# Steuerung.net
KiCad netlist of a schematic drawn in EAGLE
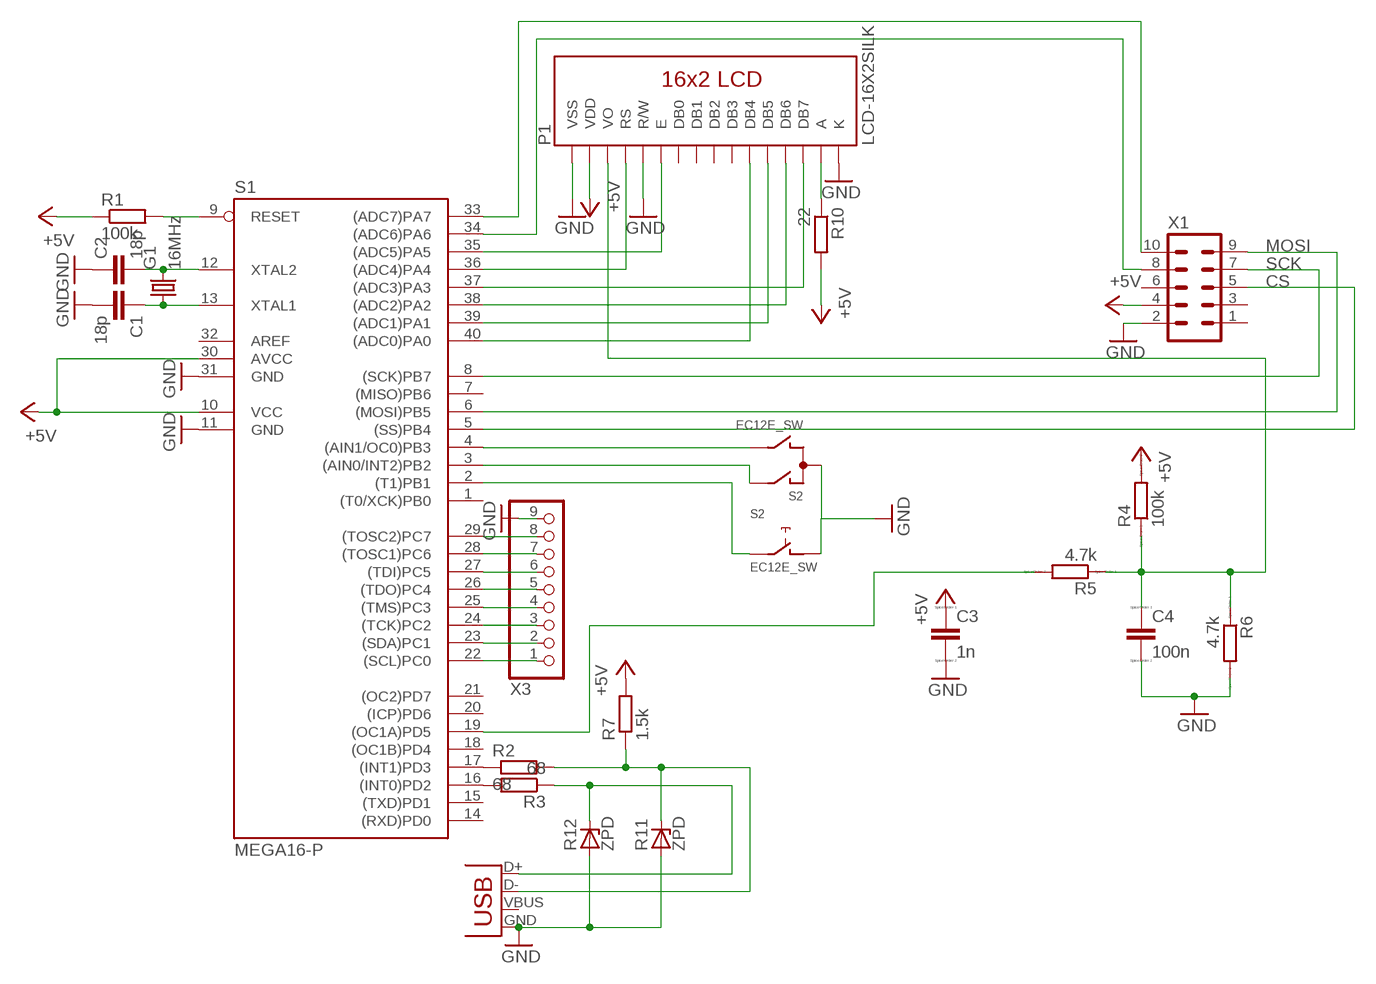
[diagram p0: schematic, sheet 1]

(export (version "E")
  (design (tool "Eeschema 10.0.6"))
  (components
    (comp (ref "C1")
      (value "18p")
      (footprint "eagle-import:C2.5-3")
      (libsource (lib "eagle-import") (part "C2,5-3"))
    )
    (comp (ref "C2")
      (value "18p")
      (footprint "eagle-import:C2.5-3")
      (libsource (lib "eagle-import") (part "C2,5-3"))
    )
    (comp (ref "C3")
      (value "1n")
      (footprint "eagle-import:C1206K")
      (libsource (lib "eagle-import") (part "C-EUC1206K"))
    )
    (comp (ref "C4")
      (value "100n")
      (footprint "eagle-import:C1206K")
      (libsource (lib "eagle-import") (part "C-EUC1206K"))
    )
    (comp (ref "G1")
      (value "16MHz")
      (footprint "eagle-import:HC18U-V")
      (libsource (lib "eagle-import") (part "CRYSTALHC18U-V"))
    )
    (comp (ref "P1")
      (value "LCD-16X2SILK")
      (footprint "eagle-import:LCD-16X2")
      (libsource (lib "eagle-import") (part "LCD-16X2SILK"))
    )
    (comp (ref "R1")
      (value "100k")
      (footprint "eagle-import:R1206W")
      (libsource (lib "eagle-import") (part "R-EU_R1206W"))
    )
    (comp (ref "R2")
      (value "68")
      (footprint "eagle-import:0309_12")
      (libsource (lib "eagle-import") (part "R-EU_0309/12"))
    )
    (comp (ref "R3")
      (value "68")
      (footprint "eagle-import:0309_12")
      (libsource (lib "eagle-import") (part "R-EU_0309/12"))
    )
    (comp (ref "R4")
      (value "100k")
      (footprint "eagle-import:R1206W")
      (libsource (lib "eagle-import") (part "resistor_R-EU_R1206W"))
    )
    (comp (ref "R5")
      (value "4.7k")
      (footprint "eagle-import:R1206W")
      (libsource (lib "eagle-import") (part "resistor_R-EU_R1206W"))
    )
    (comp (ref "R6")
      (value "4.7k")
      (footprint "eagle-import:R1206W")
      (libsource (lib "eagle-import") (part "resistor_R-EU_R1206W"))
    )
    (comp (ref "R7")
      (value "1.5k")
      (footprint "eagle-import:0309_12")
      (libsource (lib "eagle-import") (part "R-EU_0309/12"))
    )
    (comp (ref "R10")
      (value "22")
      (footprint "eagle-import:0309_12")
      (libsource (lib "eagle-import") (part "R-EU_0309/12"))
    )
    (comp (ref "R11")
      (value "ZPD")
      (footprint "eagle-import:DO35Z10")
      (libsource (lib "eagle-import") (part "ZPD"))
    )
    (comp (ref "R12")
      (value "ZPD")
      (footprint "eagle-import:DO35Z10")
      (libsource (lib "eagle-import") (part "ZPD"))
    )
    (comp (ref "S1")
      (value "MEGA16-P")
      (footprint "eagle-import:DIL40")
      (fields (field (name "MPN") "ATMEGA16-16PU") (field (name "MF") "ATMEL"))
      (libsource (lib "eagle-import") (part "MEGA16-P"))
    )
    (comp (ref "S2")
      (value "EC12E_SW")
      (footprint "eagle-import:ALPS_EC12E_SW")
      (fields (field (name "MPN") "EC12E2424407"))
      (libsource (lib "eagle-import") (part "EC12E_SW"))
    )
    (comp (ref "X1")
      (value "ML10")
      (footprint "eagle-import:ML10")
      (libsource (lib "eagle-import") (part "ML10"))
    )
    (comp (ref "X2")
      (value "USBPTH-VERTICAL")
      (footprint "eagle-import:USB-B-PTH-VERTICAL")
      (libsource (lib "eagle-import") (part "USBPTH-VERTICAL"))
    )
    (comp (ref "X3")
      (value "PINHD-1X9")
      (footprint "eagle-import:1X09")
      (libsource (lib "eagle-import") (part "PINHD-1X9"))
    )
  )
  (nets
    (net (code "1") (name "+5V") (class "Default")
      (node (ref "C3") (pin "1") (pinfunction "1_1") (pintype "passive"))
      (node (ref "P1") (pin "2") (pinfunction "VDD_2") (pintype "power_in"))
      (node (ref "R1") (pin "1") (pinfunction "1_1") (pintype "passive"))
      (node (ref "R10") (pin "2") (pinfunction "2_2") (pintype "passive"))
      (node (ref "R4") (pin "2") (pinfunction "2_2") (pintype "passive"))
      (node (ref "R7") (pin "2") (pinfunction "2_2") (pintype "passive"))
      (node (ref "S1") (pin "10") (pinfunction "VCC_10") (pintype "power_in"))
      (node (ref "S1") (pin "30") (pinfunction "AVCC_30") (pintype "power_in"))
      (node (ref "X1") (pin "4") (pinfunction "4_4") (pintype "passive"))
    )
    (net (code "2") (name "/CS") (class "Default")
      (node (ref "S1") (pin "5") (pinfunction "(SS)PB4_5") (pintype "bidirectional"))
      (node (ref "X1") (pin "5") (pinfunction "5_5") (pintype "passive"))
    )
    (net (code "3") (name "/MOSI") (class "Default")
      (node (ref "S1") (pin "6") (pinfunction "(MOSI)PB5_6") (pintype "bidirectional"))
      (node (ref "X1") (pin "9") (pinfunction "9_9") (pintype "passive"))
    )
    (net (code "4") (name "/SCK") (class "Default")
      (node (ref "S1") (pin "8") (pinfunction "(SCK)PB7_8") (pintype "bidirectional"))
      (node (ref "X1") (pin "7") (pinfunction "7_7") (pintype "passive"))
    )
    (net (code "5") (name "GND") (class "Default")
      (node (ref "C1") (pin "2") (pinfunction "2_2") (pintype "passive"))
      (node (ref "C2") (pin "1") (pinfunction "1_1") (pintype "passive"))
      (node (ref "C3") (pin "2") (pinfunction "2_2") (pintype "passive"))
      (node (ref "C4") (pin "2") (pinfunction "2_2") (pintype "passive"))
      (node (ref "P1") (pin "1") (pinfunction "VSS_1") (pintype "power_in"))
      (node (ref "P1") (pin "16") (pinfunction "K_16") (pintype "power_in"))
      (node (ref "P1") (pin "5") (pinfunction "R/W_5") (pintype "input"))
      (node (ref "R11") (pin "A") (pinfunction "A_A") (pintype "passive"))
      (node (ref "R12") (pin "A") (pinfunction "A_A") (pintype "passive"))
      (node (ref "R6") (pin "2") (pinfunction "2_2") (pintype "passive"))
      (node (ref "S1") (pin "11") (pinfunction "GND_11") (pintype "power_in"))
      (node (ref "S1") (pin "31") (pinfunction "GND_31") (pintype "power_in"))
      (node (ref "S2") (pin "C") (pinfunction "C_C") (pintype "passive"))
      (node (ref "S2") (pin "D") (pinfunction "1_D") (pintype "passive"))
      (node (ref "X1") (pin "2") (pinfunction "2_2") (pintype "passive"))
      (node (ref "X2") (pin "GND") (pinfunction "GND_GND") (pintype "bidirectional"))
      (node (ref "X3") (pin "9") (pinfunction "9_9") (pintype "passive"))
    )
    (net (code "6") (name "Net-(P1-A)") (class "Default")
      (node (ref "P1") (pin "15") (pinfunction "A_15") (pintype "power_in"))
      (node (ref "R10") (pin "1") (pinfunction "1_1") (pintype "passive"))
    )
    (net (code "7") (name "Net-(P1-DB4)") (class "Default")
      (node (ref "P1") (pin "11") (pinfunction "DB4_11") (pintype "bidirectional"))
      (node (ref "S1") (pin "40") (pinfunction "(ADC0)PA0_40") (pintype "bidirectional"))
    )
    (net (code "8") (name "Net-(P1-DB5)") (class "Default")
      (node (ref "P1") (pin "12") (pinfunction "DB5_12") (pintype "bidirectional"))
      (node (ref "S1") (pin "39") (pinfunction "(ADC1)PA1_39") (pintype "bidirectional"))
    )
    (net (code "9") (name "Net-(P1-DB6)") (class "Default")
      (node (ref "P1") (pin "13") (pinfunction "DB6_13") (pintype "bidirectional"))
      (node (ref "S1") (pin "38") (pinfunction "(ADC2)PA2_38") (pintype "bidirectional"))
    )
    (net (code "10") (name "Net-(P1-DB7)") (class "Default")
      (node (ref "P1") (pin "14") (pinfunction "DB7_14") (pintype "bidirectional"))
      (node (ref "S1") (pin "37") (pinfunction "(ADC3)PA3_37") (pintype "bidirectional"))
    )
    (net (code "11") (name "Net-(P1-E)") (class "Default")
      (node (ref "P1") (pin "6") (pinfunction "E_6") (pintype "input"))
      (node (ref "S1") (pin "35") (pinfunction "(ADC5)PA5_35") (pintype "bidirectional"))
    )
    (net (code "12") (name "Net-(P1-RS)") (class "Default")
      (node (ref "P1") (pin "4") (pinfunction "RS_4") (pintype "input"))
      (node (ref "S1") (pin "36") (pinfunction "(ADC4)PA4_36") (pintype "bidirectional"))
    )
    (net (code "13") (name "Net-(P1-VO)") (class "Default")
      (node (ref "C4") (pin "1") (pinfunction "1_1") (pintype "passive"))
      (node (ref "P1") (pin "3") (pinfunction "VO_3") (pintype "bidirectional"))
      (node (ref "R4") (pin "1") (pinfunction "1_1") (pintype "passive"))
      (node (ref "R5") (pin "1") (pinfunction "1_1") (pintype "passive"))
      (node (ref "R6") (pin "1") (pinfunction "1_1") (pintype "passive"))
    )
    (net (code "14") (name "Net-(R11-PadC)") (class "Default")
      (node (ref "R11") (pin "C") (pinfunction "C_C") (pintype "passive"))
      (node (ref "R2") (pin "2") (pinfunction "2_2") (pintype "passive"))
      (node (ref "R7") (pin "1") (pinfunction "1_1") (pintype "passive"))
      (node (ref "X2") (pin "D-") (pinfunction "D-_D-") (pintype "bidirectional"))
    )
    (net (code "15") (name "Net-(R12-PadC)") (class "Default")
      (node (ref "R12") (pin "C") (pinfunction "C_C") (pintype "passive"))
      (node (ref "R3") (pin "1") (pinfunction "1_1") (pintype "passive"))
      (node (ref "X2") (pin "D+") (pinfunction "D+_D+") (pintype "bidirectional"))
    )
    (net (code "16") (name "Net-(S1-(ADC6)PA6)") (class "Default")
      (node (ref "S1") (pin "34") (pinfunction "(ADC6)PA6_34") (pintype "bidirectional"))
      (node (ref "X1") (pin "8") (pinfunction "8_8") (pintype "passive"))
    )
    (net (code "17") (name "Net-(S1-(ADC7)PA7)") (class "Default")
      (node (ref "S1") (pin "33") (pinfunction "(ADC7)PA7_33") (pintype "bidirectional"))
      (node (ref "X1") (pin "10") (pinfunction "10_10") (pintype "passive"))
    )
    (net (code "18") (name "Net-(S1-(AIN0{slash}INT2)PB2)") (class "Default")
      (node (ref "S1") (pin "3") (pinfunction "(AIN0/INT2)PB2_3") (pintype "bidirectional"))
      (node (ref "S2") (pin "A") (pinfunction "A_A") (pintype "passive"))
    )
    (net (code "19") (name "Net-(S1-(AIN1{slash}OC0)PB3)") (class "Default")
      (node (ref "S1") (pin "4") (pinfunction "(AIN1/OC0)PB3_4") (pintype "bidirectional"))
      (node (ref "S2") (pin "B") (pinfunction "B_B") (pintype "passive"))
    )
    (net (code "20") (name "Net-(S1-(INT0)PD2)") (class "Default")
      (node (ref "R3") (pin "2") (pinfunction "2_2") (pintype "passive"))
      (node (ref "S1") (pin "16") (pinfunction "(INT0)PD2_16") (pintype "bidirectional"))
    )
    (net (code "21") (name "Net-(S1-(INT1)PD3)") (class "Default")
      (node (ref "R2") (pin "1") (pinfunction "1_1") (pintype "passive"))
      (node (ref "S1") (pin "17") (pinfunction "(INT1)PD3_17") (pintype "bidirectional"))
    )
    (net (code "22") (name "Net-(S1-(OC1A)PD5)") (class "Default")
      (node (ref "R5") (pin "2") (pinfunction "2_2") (pintype "passive"))
      (node (ref "S1") (pin "19") (pinfunction "(OC1A)PD5_19") (pintype "bidirectional"))
    )
    (net (code "23") (name "Net-(S1-(SCL)PC0)") (class "Default")
      (node (ref "S1") (pin "22") (pinfunction "(SCL)PC0_22") (pintype "bidirectional"))
      (node (ref "X3") (pin "1") (pinfunction "1_1") (pintype "passive"))
    )
    (net (code "24") (name "Net-(S1-(SDA)PC1)") (class "Default")
      (node (ref "S1") (pin "23") (pinfunction "(SDA)PC1_23") (pintype "bidirectional"))
      (node (ref "X3") (pin "2") (pinfunction "2_2") (pintype "passive"))
    )
    (net (code "25") (name "Net-(S1-(T1)PB1)") (class "Default")
      (node (ref "S1") (pin "2") (pinfunction "(T1)PB1_2") (pintype "bidirectional"))
      (node (ref "S2") (pin "E") (pinfunction "2_E") (pintype "passive"))
    )
    (net (code "26") (name "Net-(S1-(TCK)PC2)") (class "Default")
      (node (ref "S1") (pin "24") (pinfunction "(TCK)PC2_24") (pintype "bidirectional"))
      (node (ref "X3") (pin "3") (pinfunction "3_3") (pintype "passive"))
    )
    (net (code "27") (name "Net-(S1-(TDI)PC5)") (class "Default")
      (node (ref "S1") (pin "27") (pinfunction "(TDI)PC5_27") (pintype "bidirectional"))
      (node (ref "X3") (pin "6") (pinfunction "6_6") (pintype "passive"))
    )
    (net (code "28") (name "Net-(S1-(TDO)PC4)") (class "Default")
      (node (ref "S1") (pin "26") (pinfunction "(TDO)PC4_26") (pintype "bidirectional"))
      (node (ref "X3") (pin "5") (pinfunction "5_5") (pintype "passive"))
    )
    (net (code "29") (name "Net-(S1-(TMS)PC3)") (class "Default")
      (node (ref "S1") (pin "25") (pinfunction "(TMS)PC3_25") (pintype "bidirectional"))
      (node (ref "X3") (pin "4") (pinfunction "4_4") (pintype "passive"))
    )
    (net (code "30") (name "Net-(S1-(TOSC1)PC6)") (class "Default")
      (node (ref "S1") (pin "28") (pinfunction "(TOSC1)PC6_28") (pintype "bidirectional"))
      (node (ref "X3") (pin "7") (pinfunction "7_7") (pintype "passive"))
    )
    (net (code "31") (name "Net-(S1-(TOSC2)PC7)") (class "Default")
      (node (ref "S1") (pin "29") (pinfunction "(TOSC2)PC7_29") (pintype "bidirectional"))
      (node (ref "X3") (pin "8") (pinfunction "8_8") (pintype "passive"))
    )
    (net (code "32") (name "Net-(S1-RESET)") (class "Default")
      (node (ref "R1") (pin "2") (pinfunction "2_2") (pintype "passive"))
      (node (ref "S1") (pin "9") (pinfunction "RESET_9") (pintype "input"))
    )
    (net (code "33") (name "Net-(S1-XTAL1)") (class "Default")
      (node (ref "C1") (pin "1") (pinfunction "1_1") (pintype "passive"))
      (node (ref "G1") (pin "1") (pinfunction "1_1") (pintype "passive"))
      (node (ref "S1") (pin "13") (pinfunction "XTAL1_13") (pintype "bidirectional"))
    )
    (net (code "34") (name "Net-(S1-XTAL2)") (class "Default")
      (node (ref "C2") (pin "2") (pinfunction "2_2") (pintype "passive"))
      (node (ref "G1") (pin "2") (pinfunction "2_2") (pintype "passive"))
      (node (ref "S1") (pin "12") (pinfunction "XTAL2_12") (pintype "bidirectional"))
    )
    (net (code "35") (name "unconnected-(P1-DB0-Pad7)") (class "Default")
      (node (ref "P1") (pin "7") (pinfunction "DB0_7") (pintype "bidirectional"))
    )
    (net (code "36") (name "unconnected-(P1-DB1-Pad8)") (class "Default")
      (node (ref "P1") (pin "8") (pinfunction "DB1_8") (pintype "bidirectional"))
    )
    (net (code "37") (name "unconnected-(P1-DB2-Pad9)") (class "Default")
      (node (ref "P1") (pin "9") (pinfunction "DB2_9") (pintype "bidirectional"))
    )
    (net (code "38") (name "unconnected-(P1-DB3-Pad10)") (class "Default")
      (node (ref "P1") (pin "10") (pinfunction "DB3_10") (pintype "bidirectional"))
    )
    (net (code "39") (name "unconnected-(S1-(ICP)PD6-Pad20)") (class "Default")
      (node (ref "S1") (pin "20") (pinfunction "(ICP)PD6_20") (pintype "bidirectional"))
    )
    (net (code "40") (name "unconnected-(S1-(MISO)PB6-Pad7)") (class "Default")
      (node (ref "S1") (pin "7") (pinfunction "(MISO)PB6_7") (pintype "bidirectional"))
    )
    (net (code "41") (name "unconnected-(S1-(OC1B)PD4-Pad18)") (class "Default")
      (node (ref "S1") (pin "18") (pinfunction "(OC1B)PD4_18") (pintype "bidirectional"))
    )
    (net (code "42") (name "unconnected-(S1-(OC2)PD7-Pad21)") (class "Default")
      (node (ref "S1") (pin "21") (pinfunction "(OC2)PD7_21") (pintype "bidirectional"))
    )
    (net (code "43") (name "unconnected-(S1-(RXD)PD0-Pad14)") (class "Default")
      (node (ref "S1") (pin "14") (pinfunction "(RXD)PD0_14") (pintype "bidirectional"))
    )
    (net (code "44") (name "unconnected-(S1-(T0{slash}XCK)PB0-Pad1)") (class "Default")
      (node (ref "S1") (pin "1") (pinfunction "(T0/XCK)PB0_1") (pintype "bidirectional"))
    )
    (net (code "45") (name "unconnected-(S1-(TXD)PD1-Pad15)") (class "Default")
      (node (ref "S1") (pin "15") (pinfunction "(TXD)PD1_15") (pintype "bidirectional"))
    )
    (net (code "46") (name "unconnected-(S1-AREF-Pad32)") (class "Default")
      (node (ref "S1") (pin "32") (pinfunction "AREF_32") (pintype "passive"))
    )
    (net (code "47") (name "unconnected-(X1-Pad1)") (class "Default")
      (node (ref "X1") (pin "1") (pinfunction "1_1") (pintype "passive"))
    )
    (net (code "48") (name "unconnected-(X1-Pad3)") (class "Default")
      (node (ref "X1") (pin "3") (pinfunction "3_3") (pintype "passive"))
    )
    (net (code "49") (name "unconnected-(X1-Pad6)") (class "Default")
      (node (ref "X1") (pin "6") (pinfunction "6_6") (pintype "passive"))
    )
    (net (code "50") (name "unconnected-(X2-PadVBUS)") (class "Default")
      (node (ref "X2") (pin "VBUS") (pinfunction "VBUS_VBUS") (pintype "bidirectional"))
    )
  )
)
